# STM32F407VG_A.net
KiCad netlist of a schematic drawn in Altium Designer
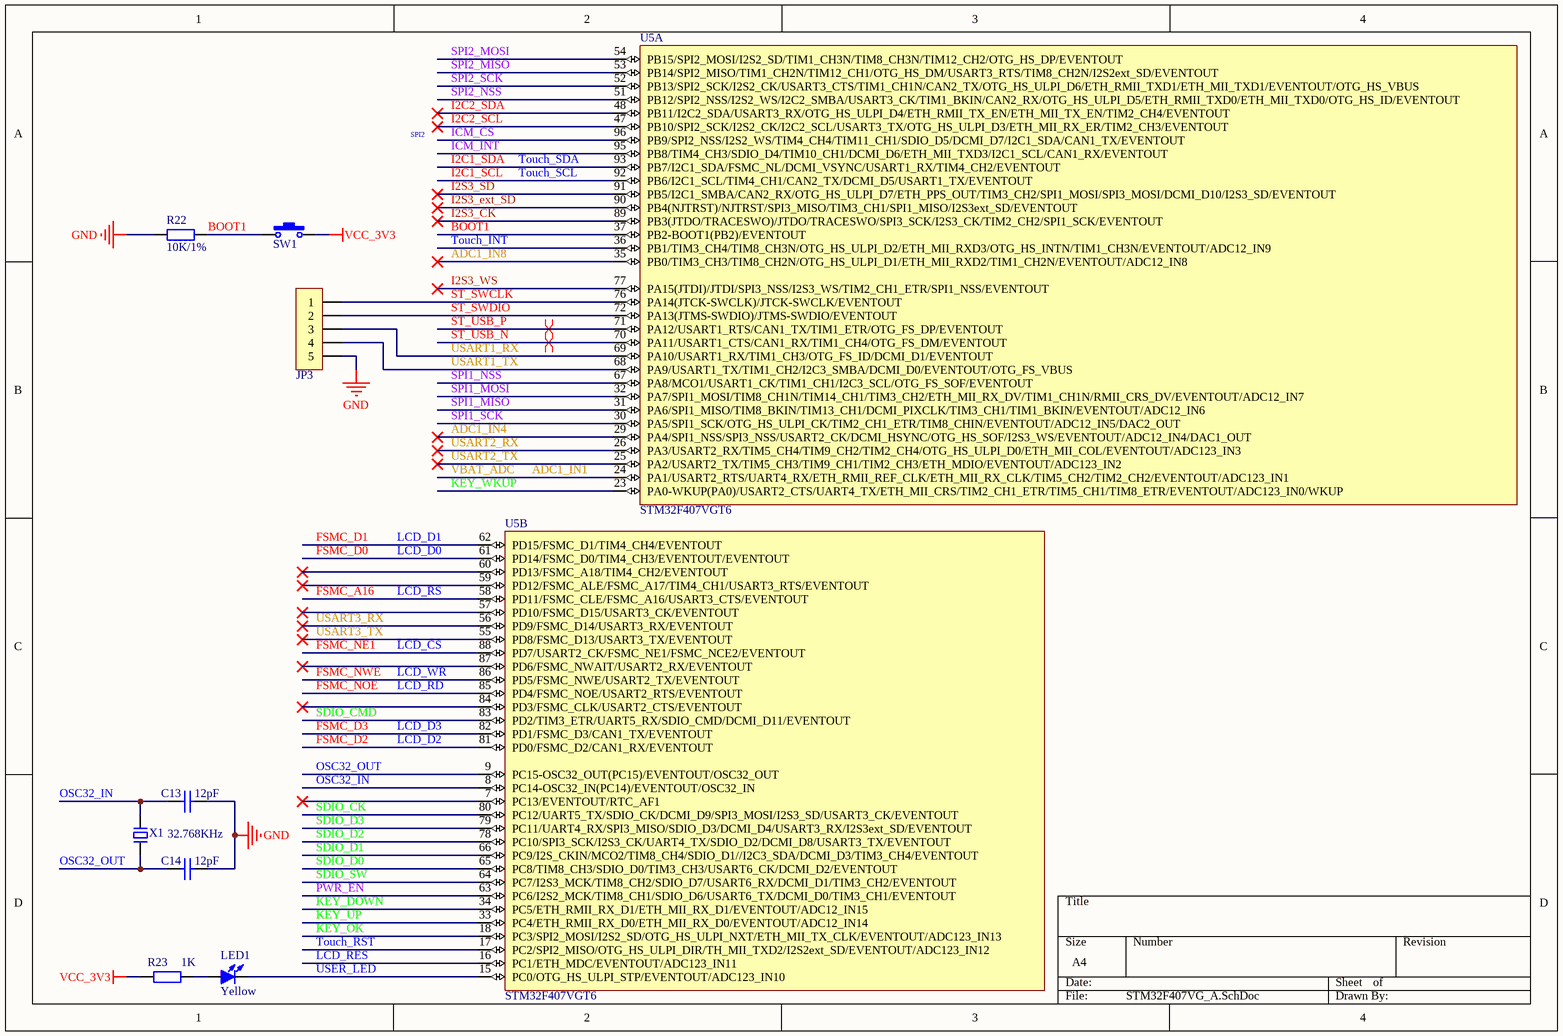
[diagram p0: STM32F407VG_A.SchDoc]

(export (version "E")
  (design (tool "Eeschema 10.0.6"))
  (components
    (comp (ref "C13")
      (value "12pF")
      (footprint "C0402_L")
      (description "贴片电容")
      (libsource (lib "0.1 - 电阻-电容-电感-晶振-晶体-磁珠-电位器") (part "C"))
    )
    (comp (ref "C14")
      (value "12pF")
      (footprint "C0402_L")
      (description "贴片电容")
      (libsource (lib "0.1 - 电阻-电容-电感-晶振-晶体-磁珠-电位器") (part "C"))
    )
    (comp (ref "JP3")
      (value "HDR-1X5")
      (footprint "HDR1.27-LI-5P")
      (description "5P接插件")
      (libsource (lib "5.4 - 2.0mm连接器(排针排母)") (part "Header 5"))
    )
    (comp (ref "LED1")
      (value "Yellow")
      (footprint "LED0402")
      (description "贴片LED")
      (libsource (lib "0.3 - LED发光二极管-IR二极管_接收管-光耦") (part "LED-SMD"))
    )
    (comp (ref "R22")
      (value "10K/1%")
      (footprint "R0402_L")
      (description "贴片电阻")
      (libsource (lib "0.1 - 电阻-电容-电感-晶振-晶体-磁珠-电位器") (part "R"))
    )
    (comp (ref "R23")
      (value "1K")
      (footprint "R0402_L")
      (description "贴片电阻")
      (libsource (lib "0.1 - 电阻-电容-电感-晶振-晶体-磁珠-电位器") (part "R"))
    )
    (comp (ref "SW1")
      (value "小龟按键")
      (footprint "3*4两脚小龟按键")
      (description "微动开关")
      (libsource (lib "0.5 - 按键-开关-蜂鸣器-保险丝-电池-测试点-Mark点") (part "SW-PB"))
    )
    (comp (ref "U5")
      (value "STM32F407VGT6")
      (footprint "LQFP100_L")
      (libsource (lib "2.7 - STM32 F4系列单片机") (part "STM32F407VGT6"))
    )
    (comp (ref "X1")
      (value "32.768KHz")
      (footprint "XTAL-3215-2P")
      (description "2脚无源晶振(谐振器）")
      (libsource (lib "0.1 - 电阻-电容-电感-晶振-晶体-磁珠-电位器") (part "XTAL-2P"))
    )
  )
  (nets
    (net (code "1") (name "/ADC1_IN1") (class "Default")
      (node (ref "U5") (pin "24") (pinfunction "PA1/USART2_RTS/UART4_RX/ETH_RMII_REF_CLK/ETH_MII_RX_CLK/TIM5_CH2/TIM2_CH2/EVENTOUT/ADC123_IN1_24") (pintype "bidirectional"))
    )
    (net (code "2") (name "/ADC1_IN4") (class "Default")
      (node (ref "U5") (pin "29") (pinfunction "PA4/SPI1_NSS/SPI3_NSS/USART2_CK/DCMI_HSYNC/OTG_HS_SOF/I2S3_WS/EVENTOUT/ADC12_IN4/DAC1_OUT_29") (pintype "bidirectional+no_connect"))
    )
    (net (code "3") (name "/ADC1_IN8") (class "Default")
      (node (ref "U5") (pin "35") (pinfunction "PB0/TIM3_CH3/TIM8_CH2N/OTG_HS_ULPI_D1/ETH_MII_RXD2/TIM1_CH2N/EVENTOUT/ADC12_IN8_35") (pintype "bidirectional+no_connect"))
    )
    (net (code "4") (name "/BOOT1") (class "Default")
      (node (ref "R22") (pin "2") (pinfunction "2_2") (pintype "passive"))
      (node (ref "SW1") (pin "1") (pinfunction "1_1") (pintype "passive"))
      (node (ref "U5") (pin "37") (pinfunction "PB2-BOOT1(PB2)/EVENTOUT_37") (pintype "bidirectional"))
    )
    (net (code "5") (name "/FSMC_A16") (class "Default")
      (node (ref "U5") (pin "58") (pinfunction "PD11/FSMC_CLE/FSMC_A16/USART3_CTS/EVENTOUT_58") (pintype "bidirectional"))
    )
    (net (code "6") (name "/FSMC_D0") (class "Default")
      (node (ref "U5") (pin "61") (pinfunction "PD14/FSMC_D0/TIM4_CH3/EVENTOUT/EVENTOUT_61") (pintype "bidirectional"))
    )
    (net (code "7") (name "/FSMC_D1") (class "Default")
      (node (ref "U5") (pin "62") (pinfunction "PD15/FSMC_D1/TIM4_CH4/EVENTOUT_62") (pintype "bidirectional"))
    )
    (net (code "8") (name "/FSMC_D2") (class "Default")
      (node (ref "U5") (pin "81") (pinfunction "PD0/FSMC_D2/CAN1_RX/EVENTOUT_81") (pintype "bidirectional"))
    )
    (net (code "9") (name "/FSMC_D3") (class "Default")
      (node (ref "U5") (pin "82") (pinfunction "PD1/FSMC_D3/CAN1_TX/EVENTOUT_82") (pintype "bidirectional"))
    )
    (net (code "10") (name "/FSMC_NE1") (class "Default")
      (node (ref "U5") (pin "88") (pinfunction "PD7/USART2_CK/FSMC_NE1/FSMC_NCE2/EVENTOUT_88") (pintype "bidirectional"))
    )
    (net (code "11") (name "/FSMC_NOE") (class "Default")
      (node (ref "U5") (pin "85") (pinfunction "PD4/FSMC_NOE/USART2_RTS/EVENTOUT_85") (pintype "bidirectional"))
    )
    (net (code "12") (name "/FSMC_NWE") (class "Default")
      (node (ref "U5") (pin "86") (pinfunction "PD5/FSMC_NWE/USART2_TX/EVENTOUT_86") (pintype "bidirectional"))
    )
    (net (code "13") (name "/I2C1_SCL") (class "Default")
      (node (ref "U5") (pin "92") (pinfunction "PB6/I2C1_SCL/TIM4_CH1/CAN2_TX/DCMI_D5/USART1_TX/EVENTOUT_92") (pintype "bidirectional"))
    )
    (net (code "14") (name "/I2C1_SDA") (class "Default")
      (node (ref "U5") (pin "93") (pinfunction "PB7/I2C1_SDA/FSMC_NL/DCMI_VSYNC/USART1_RX/TIM4_CH2/EVENTOUT_93") (pintype "bidirectional"))
    )
    (net (code "15") (name "/I2C2_SCL") (class "Default")
      (node (ref "U5") (pin "47") (pinfunction "PB10/SPI2_SCK/I2S2_CK/I2C2_SCL/USART3_TX/OTG_HS_ULPI_D3/ETH_MII_RX_ER/TIM2_CH3/EVENTOUT_47") (pintype "bidirectional+no_connect"))
    )
    (net (code "16") (name "/I2C2_SDA") (class "Default")
      (node (ref "U5") (pin "48") (pinfunction "PB11/I2C2_SDA/USART3_RX/OTG_HS_ULPI_D4/ETH_RMII_TX_EN/ETH_MII_TX_EN/TIM2_CH4/EVENTOUT_48") (pintype "bidirectional+no_connect"))
    )
    (net (code "17") (name "/I2S3_CK") (class "Default")
      (node (ref "U5") (pin "89") (pinfunction "PB3(JTDO/TRACESWO)/JTDO/TRACESWO/SPI3_SCK/I2S3_CK/TIM2_CH2/SPI1_SCK/EVENTOUT_89") (pintype "bidirectional+no_connect"))
    )
    (net (code "18") (name "/I2S3_SD") (class "Default")
      (node (ref "U5") (pin "91") (pinfunction "PB5/I2C1_SMBA/CAN2_RX/OTG_HS_ULPI_D7/ETH_PPS_OUT/TIM3_CH2/SPI1_MOSI/SPI3_MOSI/DCMI_D10/I2S3_SD/EVENTOUT_91") (pintype "bidirectional+no_connect"))
    )
    (net (code "19") (name "/I2S3_WS") (class "Default")
      (node (ref "U5") (pin "77") (pinfunction "PA15(JTDI)/JTDI/SPI3_NSS/I2S3_WS/TIM2_CH1_ETR/SPI1_NSS/EVENTOUT_77") (pintype "bidirectional+no_connect"))
    )
    (net (code "20") (name "/I2S3_ext_SD") (class "Default")
      (node (ref "U5") (pin "90") (pinfunction "PB4(NJTRST)/NJTRST/SPI3_MISO/TIM3_CH1/SPI1_MISO/I2S3ext_SD/EVENTOUT_90") (pintype "bidirectional+no_connect"))
    )
    (net (code "21") (name "/ICM_CS") (class "Default")
      (node (ref "U5") (pin "96") (pinfunction "PB9/SPI2_NSS/I2S2_WS/TIM4_CH4/TIM11_CH1/SDIO_D5/DCMI_D7/I2C1_SDA/CAN1_TX/EVENTOUT_96") (pintype "bidirectional"))
    )
    (net (code "22") (name "/ICM_INT") (class "Default")
      (node (ref "U5") (pin "95") (pinfunction "PB8/TIM4_CH3/SDIO_D4/TIM10_CH1/DCMI_D6/ETH_MII_TXD3/I2C1_SCL/CAN1_RX/EVENTOUT_95") (pintype "bidirectional"))
    )
    (net (code "23") (name "/KEY_DOWN") (class "Default")
      (node (ref "U5") (pin "34") (pinfunction "PC5/ETH_RMII_RX_D1/ETH_MII_RX_D1/EVENTOUT/ADC12_IN15_34") (pintype "bidirectional"))
    )
    (net (code "24") (name "/KEY_OK") (class "Default")
      (node (ref "U5") (pin "18") (pinfunction "PC3/SPI2_MOSI/I2S2_SD/OTG_HS_ULPI_NXT/ETH_MII_TX_CLK/EVENTOUT/ADC123_IN13_18") (pintype "bidirectional"))
    )
    (net (code "25") (name "/KEY_UP") (class "Default")
      (node (ref "U5") (pin "33") (pinfunction "PC4/ETH_RMII_RX_D0/ETH_MII_RX_D0/EVENTOUT/ADC12_IN14_33") (pintype "bidirectional"))
    )
    (net (code "26") (name "/KEY_WKUP") (class "Default")
      (node (ref "U5") (pin "23") (pinfunction "PA0-WKUP(PA0)/USART2_CTS/UART4_TX/ETH_MII_CRS/TIM2_CH1_ETR/TIM5_CH1/TIM8_ETR/EVENTOUT/ADC123_IN0/WKUP_23") (pintype "bidirectional"))
    )
    (net (code "27") (name "/LCD_RES") (class "Default")
      (node (ref "U5") (pin "16") (pinfunction "PC1/ETH_MDC/EVENTOUT/ADC123_IN11_16") (pintype "bidirectional"))
    )
    (net (code "28") (name "/OSC32_IN") (class "Default")
      (node (ref "C13") (pin "2") (pinfunction "2_2") (pintype "passive"))
      (node (ref "U5") (pin "8") (pinfunction "PC14-OSC32_IN(PC14)/EVENTOUT/OSC32_IN_8") (pintype "bidirectional"))
      (node (ref "X1") (pin "2") (pinfunction "2_2") (pintype "passive"))
    )
    (net (code "29") (name "/OSC32_OUT") (class "Default")
      (node (ref "C14") (pin "2") (pinfunction "2_2") (pintype "passive"))
      (node (ref "U5") (pin "9") (pinfunction "PC15-OSC32_OUT(PC15)/EVENTOUT/OSC32_OUT_9") (pintype "bidirectional"))
      (node (ref "X1") (pin "1") (pinfunction "1_1") (pintype "passive"))
    )
    (net (code "30") (name "/PWR_EN") (class "Default")
      (node (ref "U5") (pin "63") (pinfunction "PC6/I2S2_MCK/TIM8_CH1/SDIO_D6/USART6_TX/DCMI_D0/TIM3_CH1/EVENTOUT_63") (pintype "bidirectional"))
    )
    (net (code "31") (name "/SDIO_CK") (class "Default")
      (node (ref "U5") (pin "80") (pinfunction "PC12/UART5_TX/SDIO_CK/DCMI_D9/SPI3_MOSI/I2S3_SD/USART3_CK/EVENTOUT_80") (pintype "bidirectional"))
    )
    (net (code "32") (name "/SDIO_CMD") (class "Default")
      (node (ref "U5") (pin "83") (pinfunction "PD2/TIM3_ETR/UART5_RX/SDIO_CMD/DCMI_D11/EVENTOUT_83") (pintype "bidirectional"))
    )
    (net (code "33") (name "/SDIO_D0") (class "Default")
      (node (ref "U5") (pin "65") (pinfunction "PC8/TIM8_CH3/SDIO_D0/TIM3_CH3/USART6_CK/DCMI_D2/EVENTOUT_65") (pintype "bidirectional"))
    )
    (net (code "34") (name "/SDIO_D1") (class "Default")
      (node (ref "U5") (pin "66") (pinfunction "PC9/I2S_CKIN/MCO2/TIM8_CH4/SDIO_D1//I2C3_SDA/DCMI_D3/TIM3_CH4/EVENTOUT_66") (pintype "bidirectional"))
    )
    (net (code "35") (name "/SDIO_D2") (class "Default")
      (node (ref "U5") (pin "78") (pinfunction "PC10/SPI3_SCK/I2S3_CK/UART4_TX/SDIO_D2/DCMI_D8/USART3_TX/EVENTOUT_78") (pintype "bidirectional"))
    )
    (net (code "36") (name "/SDIO_D3") (class "Default")
      (node (ref "U5") (pin "79") (pinfunction "PC11/UART4_RX/SPI3_MISO/SDIO_D3/DCMI_D4/USART3_RX/I2S3ext_SD/EVENTOUT_79") (pintype "bidirectional"))
    )
    (net (code "37") (name "/SDIO_SW") (class "Default")
      (node (ref "U5") (pin "64") (pinfunction "PC7/I2S3_MCK/TIM8_CH2/SDIO_D7/USART6_RX/DCMI_D1/TIM3_CH2/EVENTOUT_64") (pintype "bidirectional"))
    )
    (net (code "38") (name "/SPI1_MISO") (class "Default")
      (node (ref "U5") (pin "31") (pinfunction "PA6/SPI1_MISO/TIM8_BKIN/TIM13_CH1/DCMI_PIXCLK/TIM3_CH1/TIM1_BKIN/EVENTOUT/ADC12_IN6_31") (pintype "bidirectional"))
    )
    (net (code "39") (name "/SPI1_MOSI") (class "Default")
      (node (ref "U5") (pin "32") (pinfunction "PA7/SPI1_MOSI/TIM8_CH1N/TIM14_CH1/TIM3_CH2/ETH_MII_RX_DV/TIM1_CH1N/RMII_CRS_DV/EVENTOUT/ADC12_IN7_32") (pintype "bidirectional"))
    )
    (net (code "40") (name "/SPI1_NSS") (class "Default")
      (node (ref "U5") (pin "67") (pinfunction "PA8/MCO1/USART1_CK/TIM1_CH1/I2C3_SCL/OTG_FS_SOF/EVENTOUT_67") (pintype "bidirectional"))
    )
    (net (code "41") (name "/SPI1_SCK") (class "Default")
      (node (ref "U5") (pin "30") (pinfunction "PA5/SPI1_SCK/OTG_HS_ULPI_CK/TIM2_CH1_ETR/TIM8_CHIN/EVENTOUT/ADC12_IN5/DAC2_OUT_30") (pintype "bidirectional"))
    )
    (net (code "42") (name "/SPI2_MISO") (class "Default")
      (node (ref "U5") (pin "53") (pinfunction "PB14/SPI2_MISO/TIM1_CH2N/TIM12_CH1/OTG_HS_DM/USART3_RTS/TIM8_CH2N/I2S2ext_SD/EVENTOUT_53") (pintype "bidirectional"))
    )
    (net (code "43") (name "/SPI2_MOSI") (class "Default")
      (node (ref "U5") (pin "54") (pinfunction "PB15/SPI2_MOSI/I2S2_SD/TIM1_CH3N/TIM8_CH3N/TIM12_CH2/OTG_HS_DP/EVENTOUT_54") (pintype "bidirectional"))
    )
    (net (code "44") (name "/SPI2_NSS") (class "Default")
      (node (ref "U5") (pin "51") (pinfunction "PB12/SPI2_NSS/I2S2_WS/I2C2_SMBA/USART3_CK/TIM1_BKIN/CAN2_RX/OTG_HS_ULPI_D5/ETH_RMII_TXD0/ETH_MII_TXD0/OTG_HS_ID/EVENTOUT_51") (pintype "bidirectional"))
    )
    (net (code "45") (name "/SPI2_SCK") (class "Default")
      (node (ref "U5") (pin "52") (pinfunction "PB13/SPI2_SCK/I2S2_CK/USART3_CTS/TIM1_CH1N/CAN2_TX/OTG_HS_ULPI_D6/ETH_RMII_TXD1/ETH_MII_TXD1/EVENTOUT/OTG_HS_VBUS_52") (pintype "bidirectional"))
    )
    (net (code "46") (name "/ST_SWCLK") (class "Default")
      (node (ref "JP3") (pin "1") (pinfunction "1_1") (pintype "passive"))
      (node (ref "U5") (pin "76") (pinfunction "PA14(JTCK-SWCLK)/JTCK-SWCLK/EVENTOUT_76") (pintype "bidirectional"))
    )
    (net (code "47") (name "/ST_SWDIO") (class "Default")
      (node (ref "JP3") (pin "2") (pinfunction "2_2") (pintype "passive"))
      (node (ref "U5") (pin "72") (pinfunction "PA13(JTMS-SWDIO)/JTMS-SWDIO/EVENTOUT_72") (pintype "bidirectional"))
    )
    (net (code "48") (name "/ST_USB_N") (class "Default")
      (node (ref "U5") (pin "70") (pinfunction "PA11/USART1_CTS/CAN1_RX/TIM1_CH4/OTG_FS_DM/EVENTOUT_70") (pintype "bidirectional"))
    )
    (net (code "49") (name "/ST_USB_P") (class "Default")
      (node (ref "U5") (pin "71") (pinfunction "PA12/USART1_RTS/CAN1_TX/TIM1_ETR/OTG_FS_DP/EVENTOUT_71") (pintype "bidirectional"))
    )
    (net (code "50") (name "/Touch_INT") (class "Default")
      (node (ref "U5") (pin "36") (pinfunction "PB1/TIM3_CH4/TIM8_CH3N/OTG_HS_ULPI_D2/ETH_MII_RXD3/OTG_HS_INTN/TIM1_CH3N/EVENTOUT/ADC12_IN9_36") (pintype "bidirectional"))
    )
    (net (code "51") (name "/Touch_RST") (class "Default")
      (node (ref "U5") (pin "17") (pinfunction "PC2/SPI2_MISO/OTG_HS_ULPI_DIR/TH_MII_TXD2/I2S2ext_SD/EVENTOUT/ADC123_IN12_17") (pintype "bidirectional"))
    )
    (net (code "52") (name "/USART1_RX") (class "Default")
      (node (ref "JP3") (pin "3") (pinfunction "3_3") (pintype "passive"))
      (node (ref "U5") (pin "69") (pinfunction "PA10/USART1_RX/TIM1_CH3/OTG_FS_ID/DCMI_D1/EVENTOUT_69") (pintype "bidirectional"))
    )
    (net (code "53") (name "/USART1_TX") (class "Default")
      (node (ref "JP3") (pin "4") (pinfunction "4_4") (pintype "passive"))
      (node (ref "U5") (pin "68") (pinfunction "PA9/USART1_TX/TIM1_CH2/I2C3_SMBA/DCMI_D0/EVENTOUT/OTG_FS_VBUS_68") (pintype "bidirectional"))
    )
    (net (code "54") (name "/USART2_RX") (class "Default")
      (node (ref "U5") (pin "26") (pinfunction "PA3/USART2_RX/TIM5_CH4/TIM9_CH2/TIM2_CH4/OTG_HS_ULPI_D0/ETH_MII_COL/EVENTOUT/ADC123_IN3_26") (pintype "bidirectional+no_connect"))
    )
    (net (code "55") (name "/USART2_TX") (class "Default")
      (node (ref "U5") (pin "25") (pinfunction "PA2/USART2_TX/TIM5_CH3/TIM9_CH1/TIM2_CH3/ETH_MDIO/EVENTOUT/ADC123_IN2_25") (pintype "bidirectional+no_connect"))
    )
    (net (code "56") (name "/USART3_RX") (class "Default")
      (node (ref "U5") (pin "56") (pinfunction "PD9/FSMC_D14/USART3_RX/EVENTOUT_56") (pintype "bidirectional+no_connect"))
    )
    (net (code "57") (name "/USART3_TX") (class "Default")
      (node (ref "U5") (pin "55") (pinfunction "PD8/FSMC_D13/USART3_TX/EVENTOUT_55") (pintype "bidirectional+no_connect"))
    )
    (net (code "58") (name "/USER_LED") (class "Default")
      (node (ref "LED1") (pin "2") (pinfunction "K_2") (pintype "passive"))
      (node (ref "U5") (pin "15") (pinfunction "PC0/OTG_HS_ULPI_STP/EVENTOUT/ADC123_IN10_15") (pintype "bidirectional"))
    )
    (net (code "59") (name "GND") (class "Default")
      (node (ref "C13") (pin "1") (pinfunction "1_1") (pintype "passive"))
      (node (ref "C14") (pin "1") (pinfunction "1_1") (pintype "passive"))
      (node (ref "JP3") (pin "5") (pinfunction "5_5") (pintype "passive"))
      (node (ref "R22") (pin "1") (pinfunction "1_1") (pintype "passive"))
    )
    (net (code "60") (name "Net-(LED1-A)") (class "Default")
      (node (ref "LED1") (pin "1") (pinfunction "A_1") (pintype "passive"))
      (node (ref "R23") (pin "2") (pinfunction "2_2") (pintype "passive"))
    )
    (net (code "61") (name "VCC_3V3") (class "Default")
      (node (ref "R23") (pin "1") (pinfunction "1_1") (pintype "passive"))
      (node (ref "SW1") (pin "2") (pinfunction "2_2") (pintype "passive"))
    )
    (net (code "62") (name "unconnected-(U5B-PC13{slash}EVENTOUT{slash}RTC_AF1-Pad7)") (class "Default")
      (node (ref "U5") (pin "7") (pinfunction "PC13/EVENTOUT/RTC_AF1_7") (pintype "bidirectional+no_connect"))
    )
    (net (code "63") (name "unconnected-(U5B-PD3{slash}FSMC_CLK{slash}USART2_CTS{slash}EVENTOUT-Pad84)") (class "Default")
      (node (ref "U5") (pin "84") (pinfunction "PD3/FSMC_CLK/USART2_CTS/EVENTOUT_84") (pintype "bidirectional+no_connect"))
    )
    (net (code "64") (name "unconnected-(U5B-PD6{slash}FSMC_NWAIT{slash}USART2_RX{slash}EVENTOUT-Pad87)") (class "Default")
      (node (ref "U5") (pin "87") (pinfunction "PD6/FSMC_NWAIT/USART2_RX/EVENTOUT_87") (pintype "bidirectional+no_connect"))
    )
    (net (code "65") (name "unconnected-(U5B-PD10{slash}FSMC_D15{slash}USART3_CK{slash}EVENTOUT-Pad57)") (class "Default")
      (node (ref "U5") (pin "57") (pinfunction "PD10/FSMC_D15/USART3_CK/EVENTOUT_57") (pintype "bidirectional+no_connect"))
    )
    (net (code "66") (name "unconnected-(U5B-PD12{slash}FSMC_ALE{slash}FSMC_A17{slash}TIM4_CH1{slash}USART3_RTS{slash}EVENTOUT-Pad59)") (class "Default")
      (node (ref "U5") (pin "59") (pinfunction "PD12/FSMC_ALE/FSMC_A17/TIM4_CH1/USART3_RTS/EVENTOUT_59") (pintype "bidirectional+no_connect"))
    )
    (net (code "67") (name "unconnected-(U5B-PD13{slash}FSMC_A18{slash}TIM4_CH2{slash}EVENTOUT-Pad60)") (class "Default")
      (node (ref "U5") (pin "60") (pinfunction "PD13/FSMC_A18/TIM4_CH2/EVENTOUT_60") (pintype "bidirectional+no_connect"))
    )
  )
)
